# 02_SRAD_Avionics.net
KiCad netlist of a schematic drawn in Altium Designer
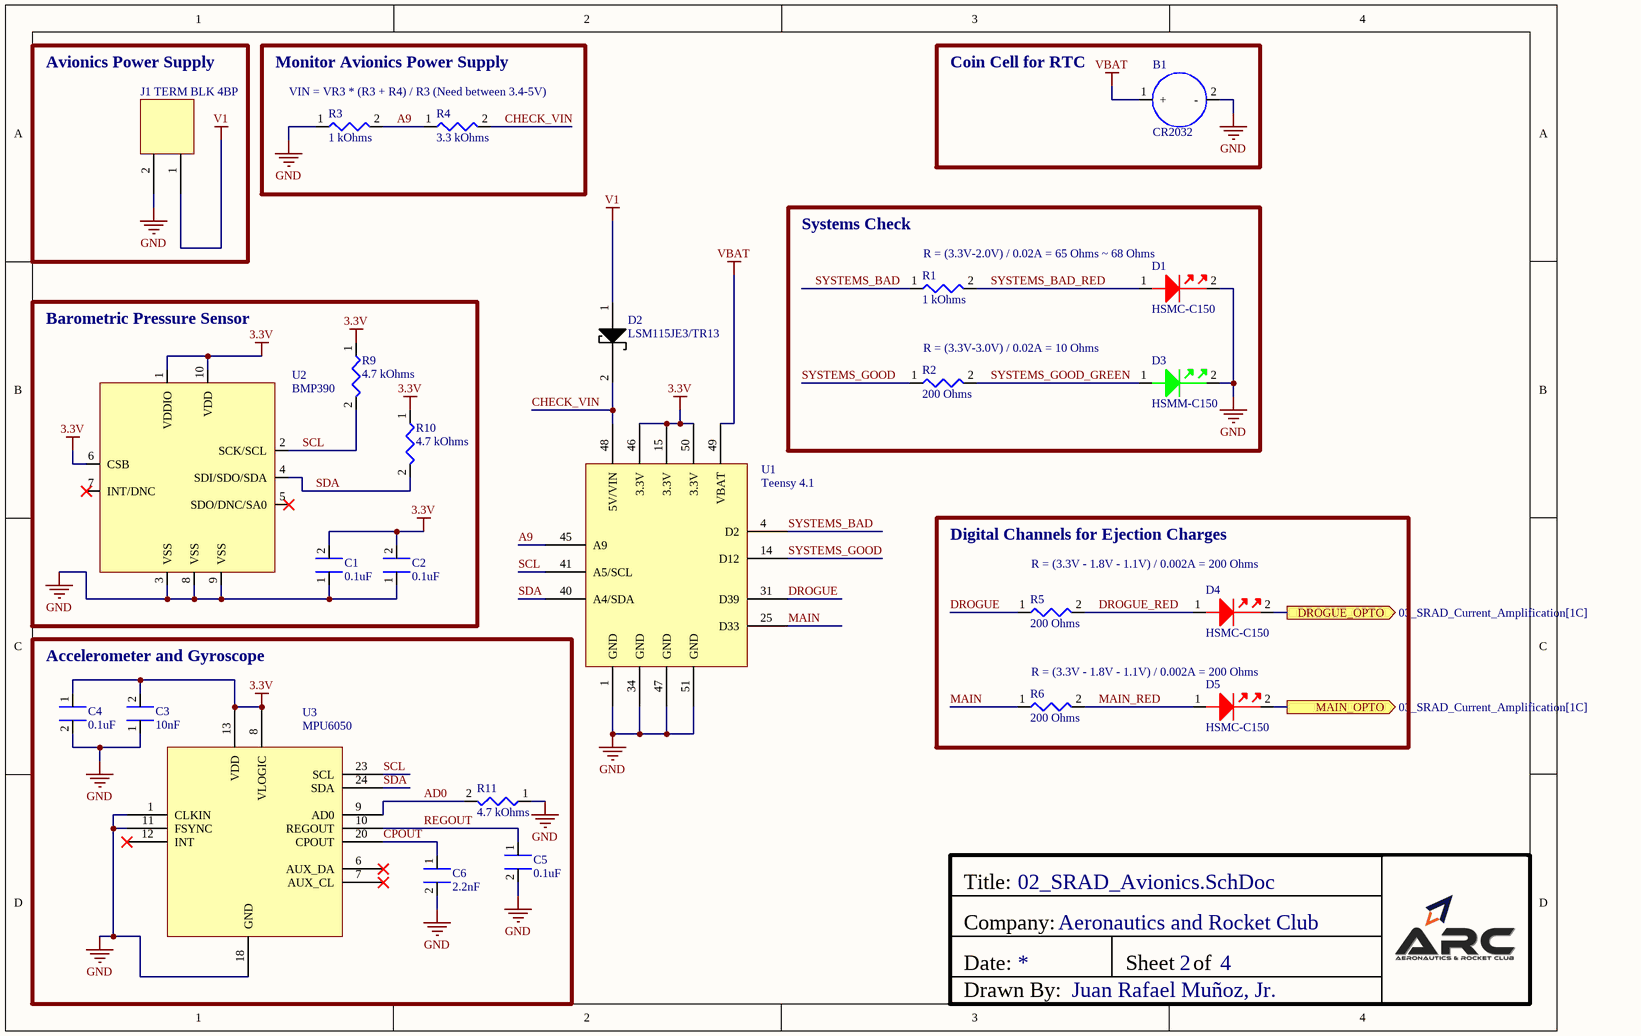
[diagram p0: 02_SRAD_Avionics.SchDoc]

(export (version "E")
  (design (tool "Eeschema 10.0.6"))
  (components
    (comp (ref "B1")
      (value "CR2032")
      (footprint "CR2032")
      (description "CR2032 Coin cell battery of 3V.")
      (libsource (lib "SRAD_SAC_Schlib") (part "CR2032"))
    )
    (comp (ref "C1")
      (value "0.1uF")
      (footprint "CAPC2012X14N_1_35mm_HEIGHT")
      (description "Capacitor Multilayer Ceramic MLCC - SMD/SMT 25 V 0.1uF X7R 0805 5%")
      (fields
        (field (name "MANUFACTURER") "Yageo")
        (field (name "MANUFACTURER PART NUMBER") "CC0805JPX7R8BB104")
      )
      (libsource (lib "SRAD_SAC_Schlib") (part "CC0805JPX7R8BB104"))
    )
    (comp (ref "C2")
      (value "0.1uF")
      (footprint "CAPC2012X14N_1_35mm_HEIGHT")
      (description "Capacitor Multilayer Ceramic MLCC - SMD/SMT 25 V 0.1uF X7R 0805 5%")
      (fields
        (field (name "MANUFACTURER") "Yageo")
        (field (name "MANUFACTURER PART NUMBER") "CC0805JPX7R8BB104")
      )
      (libsource (lib "SRAD_SAC_Schlib") (part "CC0805JPX7R8BB104"))
    )
    (comp (ref "C3")
      (value "10nF")
      (footprint "CAPC2012X07N_06mmHEIGHT")
      (description "Capacitor Multilayer Ceramic MLCC - SMD/SMT 50V 10nF X7R 0805 5%")
      (fields
        (field (name "MANUFACTURER") "Yageo")
        (field (name "MANUFACTURER PART NUMBER") "CC0805JRX7R9BB103")
      )
      (libsource (lib "SRAD_SAC_Schlib") (part "CC0805JRX7R9BB103"))
    )
    (comp (ref "C4")
      (value "0.1uF")
      (footprint "CAPC2012X14N_1_35mm_HEIGHT")
      (description "Capacitor Multilayer Ceramic MLCC - SMD/SMT 25 V 0.1uF X7R 0805 5%")
      (fields
        (field (name "MANUFACTURER") "Yageo")
        (field (name "MANUFACTURER PART NUMBER") "CC0805JPX7R8BB104")
      )
      (libsource (lib "SRAD_SAC_Schlib") (part "CC0805JPX7R8BB104"))
    )
    (comp (ref "C5")
      (value "0.1uF")
      (footprint "CAPC2012X14N_1_35mm_HEIGHT")
      (description "Capacitor Multilayer Ceramic MLCC - SMD/SMT 25 V 0.1uF X7R 0805 5%")
      (fields
        (field (name "MANUFACTURER") "Yageo")
        (field (name "MANUFACTURER PART NUMBER") "CC0805JPX7R8BB104")
      )
      (libsource (lib "SRAD_SAC_Schlib") (part "CC0805JPX7R8BB104"))
    )
    (comp (ref "C6")
      (value "2.2nF")
      (footprint "CAPC2012X07N_06mmHEIGHT")
      (description "Capacitor Multilayer Ceramic MLCC - SMD/SMT 50 V 2.2nF X7R 0805 5%")
      (fields
        (field (name "MANUFACTURER") "Yageo")
        (field (name "MANUFACTURER PART NUMBER") "CC0805JRX7R9BB222")
      )
      (libsource (lib "SRAD_SAC_Schlib") (part "CC0805JRX7R9BB222"))
    )
    (comp (ref "D1")
      (value "HSMC-C150")
      (footprint "DIOM3216X12N RED")
      (description "Red 626nm LED Indication - Discrete 1.9V 1206 (3216 Metric)")
      (fields (field (name "MANUFACTURER") "Broadcom Avago"))
      (libsource (lib "SRAD_SAC_Schlib") (part "DIOM3216X12N RED"))
    )
    (comp (ref "D2")
      (value "LSM115JE3/TR13")
      (footprint "DIOM4336X33N")
      (fields (field (name "MANUFACTURER") "Microchip"))
      (libsource (lib "SRAD_SAC_Schlib") (part "DIOM4336X33N Schottky Diode"))
    )
    (comp (ref "D3")
      (value "HSMM-C150")
      (footprint "DIOM3216X12N GREEN")
      (description "Green 525nm LED Indication - Discrete 3.3V 1206 (3216 Metric)")
      (fields (field (name "MANUFACTURER") "Broadcom Avago"))
      (libsource (lib "SRAD_SAC_Schlib") (part "DIOM3216X12N GREEN"))
    )
    (comp (ref "D4")
      (value "HSMC-C150")
      (footprint "DIOM3216X12N RED")
      (description "Red 626nm LED Indication - Discrete 1.9V 1206 (3216 Metric)")
      (fields (field (name "MANUFACTURER") "Broadcom Avago"))
      (libsource (lib "SRAD_SAC_Schlib") (part "DIOM3216X12N RED"))
    )
    (comp (ref "D5")
      (value "HSMC-C150")
      (footprint "DIOM3216X12N RED")
      (description "Red 626nm LED Indication - Discrete 1.9V 1206 (3216 Metric)")
      (fields (field (name "MANUFACTURER") "Broadcom Avago"))
      (libsource (lib "SRAD_SAC_Schlib") (part "DIOM3216X12N RED"))
    )
    (comp (ref "J1")
      (value "TERM BLK 4BP")
      (footprint "PCB TERM BLK 2P 2.54MM")
      (fields
        (field (name "MANUFACTURER") "TE Connectivity")
        (field (name "MANUFACTURER PART NUMBER") "282834-2")
        (field (name "VOLTAGE") "150V")
      )
      (libsource (lib "SRAD_SAC_Schlib") (part "PCB TERM BLK 2P 2.54MM"))
    )
    (comp (ref "R1")
      (value "1 kOhms")
      (footprint "RESC2012X06N")
      (description "1 kOhms ±1% 0.25W, 1/4W Chip Resistor 0805 (2012 Metric) Moisture Resistant Thick Film")
      (fields
        (field (name "MANUFACTURER") "Yageo")
        (field (name "MANUFACTURER PART NUMBER") "RC0805FR-7W1KL")
      )
      (libsource (lib "SRAD_SAC_Schlib") (part "RC0805FR-7W1KL Yageo"))
    )
    (comp (ref "R2")
      (value "200 Ohms")
      (footprint "RESC2012X06N")
      (description "200 Ohms ±1% 0.25W, 1/4W Chip Resistor 0805 (2012 Metric) Moisture Resistant Thick Film")
      (fields
        (field (name "MANUFACTURER") "Yageo")
        (field (name "MANUFACTURER PART NUMBER") "RC0805FR-7W200RL")
      )
      (libsource (lib "SRAD_SAC_Schlib") (part "RC0805FR-7W200RL Yageo"))
    )
    (comp (ref "R3")
      (value "1 kOhms")
      (footprint "RESC2012X06N")
      (description "1 kOhms ±1% 0.25W, 1/4W Chip Resistor 0805 (2012 Metric) Moisture Resistant Thick Film")
      (fields
        (field (name "MANUFACTURER") "Yageo")
        (field (name "MANUFACTURER PART NUMBER") "RC0805FR-7W1KL")
      )
      (libsource (lib "SRAD_SAC_Schlib") (part "RC0805FR-7W1KL Yageo"))
    )
    (comp (ref "R4")
      (value "3.3 kOhms")
      (footprint "RESC2012X06N")
      (description "3.3 kOhms ±1% 0.25W, 1/4W Chip Resistor 0805 (2012 Metric) Moisture Resistant Thick Film")
      (fields
        (field (name "MANUFACTURER") "Yageo")
        (field (name "MANUFACTURER PART NUMBER") "RC0805FR-7W3K3L")
      )
      (libsource (lib "SRAD_SAC_Schlib") (part "RC0805FR-7W3K3L Yageo"))
    )
    (comp (ref "R5")
      (value "200 Ohms")
      (footprint "RESC2012X06N")
      (description "200 Ohms ±1% 0.25W, 1/4W Chip Resistor 0805 (2012 Metric) Moisture Resistant Thick Film")
      (fields
        (field (name "MANUFACTURER") "Yageo")
        (field (name "MANUFACTURER PART NUMBER") "RC0805FR-7W200RL")
      )
      (libsource (lib "SRAD_SAC_Schlib") (part "RC0805FR-7W200RL Yageo"))
    )
    (comp (ref "R6")
      (value "200 Ohms")
      (footprint "RESC2012X06N")
      (description "200 Ohms ±1% 0.25W, 1/4W Chip Resistor 0805 (2012 Metric) Moisture Resistant Thick Film")
      (fields
        (field (name "MANUFACTURER") "Yageo")
        (field (name "MANUFACTURER PART NUMBER") "RC0805FR-7W200RL")
      )
      (libsource (lib "SRAD_SAC_Schlib") (part "RC0805FR-7W200RL Yageo"))
    )
    (comp (ref "R9")
      (value "4.7 kOhms")
      (footprint "RESC2012X06N")
      (description "4.7 kOhms ±1% 0.25W, 1/4W Chip Resistor 0805 (2012 Metric) Moisture Resistant Thick Film")
      (fields
        (field (name "MANUFACTURER") "Yageo")
        (field (name "MANUFACTURER PART NUMBER") "RC0805FR-7W4K7L")
      )
      (libsource (lib "SRAD_SAC_Schlib") (part "RC0805FR-7W4K7L Yageo"))
    )
    (comp (ref "R10")
      (value "4.7 kOhms")
      (footprint "RESC2012X06N")
      (description "4.7 kOhms ±1% 0.25W, 1/4W Chip Resistor 0805 (2012 Metric) Moisture Resistant Thick Film")
      (fields
        (field (name "MANUFACTURER") "Yageo")
        (field (name "MANUFACTURER PART NUMBER") "RC0805FR-7W4K7L")
      )
      (libsource (lib "SRAD_SAC_Schlib") (part "RC0805FR-7W4K7L Yageo"))
    )
    (comp (ref "R11")
      (value "4.7 kOhms")
      (footprint "RESC2012X06N")
      (description "4.7 kOhms ±1% 0.25W, 1/4W Chip Resistor 0805 (2012 Metric) Moisture Resistant Thick Film")
      (fields
        (field (name "MANUFACTURER") "Yageo")
        (field (name "MANUFACTURER PART NUMBER") "RC0805FR-7W4K7L")
      )
      (libsource (lib "SRAD_SAC_Schlib") (part "RC0805FR-7W4K7L Yageo"))
    )
    (comp (ref "U1")
      (value "Teensy 4.1")
      (footprint "Teensy 4.1")
      (fields (field (name "MANUFACTURER") "SparkFun") (field (name "MANUFACTURER PART NUMBER") "DEV-16996"))
      (libsource (lib "SRAD_SAC_Schlib") (part "Teensy 4.1"))
    )
    (comp (ref "U2")
      (value "BMP390")
      (footprint "BMP390")
      (description "Barometric pressure sensor manufactured by Bosch.")
      (libsource (lib "SRAD_SAC_Schlib") (part "BMP390"))
    )
    (comp (ref "U3")
      (value "MPU6050")
      (footprint "MPU6050")
      (libsource (lib "SRAD_SAC_Schlib") (part "MPU6050"))
    )
  )
  (nets
    (net (code "1") (name "/A9") (class "Default")
      (node (ref "R3") (pin "2") (pinfunction "2_2") (pintype "passive"))
      (node (ref "R4") (pin "1") (pinfunction "1_1") (pintype "passive"))
      (node (ref "U1") (pin "45") (pinfunction "A9_45") (pintype "passive"))
    )
    (net (code "2") (name "/AD0") (class "Default")
      (node (ref "R11") (pin "2") (pinfunction "2_2") (pintype "passive"))
      (node (ref "U3") (pin "9") (pinfunction "AD0_9") (pintype "passive"))
    )
    (net (code "3") (name "/CHECK_VIN") (class "Default")
      (node (ref "D2") (pin "2") (pinfunction "-_2") (pintype "passive"))
      (node (ref "R4") (pin "2") (pinfunction "2_2") (pintype "passive"))
      (node (ref "U1") (pin "48") (pinfunction "5V/VIN_48") (pintype "passive"))
    )
    (net (code "4") (name "/CPOUT") (class "Default")
      (node (ref "C6") (pin "1") (pinfunction "1_1") (pintype "passive"))
      (node (ref "U3") (pin "20") (pinfunction "CPOUT_20") (pintype "passive"))
    )
    (net (code "5") (name "/DROGUE") (class "Default")
      (node (ref "R5") (pin "1") (pinfunction "1_1") (pintype "passive"))
      (node (ref "U1") (pin "31") (pinfunction "D39_31") (pintype "passive"))
    )
    (net (code "6") (name "/DROGUE_OPTO") (class "Default")
      (node (ref "D4") (pin "2") (pinfunction "-_2") (pintype "passive"))
    )
    (net (code "7") (name "/DROGUE_RED") (class "Default")
      (node (ref "D4") (pin "1") (pinfunction "+_1") (pintype "passive"))
      (node (ref "R5") (pin "2") (pinfunction "2_2") (pintype "passive"))
    )
    (net (code "8") (name "/MAIN") (class "Default")
      (node (ref "R6") (pin "1") (pinfunction "1_1") (pintype "passive"))
      (node (ref "U1") (pin "25") (pinfunction "D33_25") (pintype "passive"))
    )
    (net (code "9") (name "/MAIN_OPTO") (class "Default")
      (node (ref "D5") (pin "2") (pinfunction "-_2") (pintype "passive"))
    )
    (net (code "10") (name "/MAIN_RED") (class "Default")
      (node (ref "D5") (pin "1") (pinfunction "+_1") (pintype "passive"))
      (node (ref "R6") (pin "2") (pinfunction "2_2") (pintype "passive"))
    )
    (net (code "11") (name "/REGOUT") (class "Default")
      (node (ref "C5") (pin "1") (pinfunction "1_1") (pintype "passive"))
      (node (ref "U3") (pin "10") (pinfunction "REGOUT_10") (pintype "passive"))
    )
    (net (code "12") (name "/SCL") (class "Default")
      (node (ref "R9") (pin "2") (pinfunction "2_2") (pintype "passive"))
      (node (ref "U1") (pin "41") (pinfunction "A5/SCL_41") (pintype "passive"))
      (node (ref "U2") (pin "2") (pinfunction "SCK/SCL_2") (pintype "passive"))
      (node (ref "U3") (pin "23") (pinfunction "SCL_23") (pintype "passive"))
    )
    (net (code "13") (name "/SDA") (class "Default")
      (node (ref "R10") (pin "2") (pinfunction "2_2") (pintype "passive"))
      (node (ref "U1") (pin "40") (pinfunction "A4/SDA_40") (pintype "passive"))
      (node (ref "U2") (pin "4") (pinfunction "SDI/SDO/SDA_4") (pintype "passive"))
      (node (ref "U3") (pin "24") (pinfunction "SDA_24") (pintype "passive"))
    )
    (net (code "14") (name "/SYSTEMS_BAD") (class "Default")
      (node (ref "R1") (pin "1") (pinfunction "1_1") (pintype "passive"))
      (node (ref "U1") (pin "4") (pinfunction "D2_4") (pintype "passive"))
    )
    (net (code "15") (name "/SYSTEMS_BAD_RED") (class "Default")
      (node (ref "D1") (pin "1") (pinfunction "+_1") (pintype "passive"))
      (node (ref "R1") (pin "2") (pinfunction "2_2") (pintype "passive"))
    )
    (net (code "16") (name "/SYSTEMS_GOOD") (class "Default")
      (node (ref "R2") (pin "1") (pinfunction "1_1") (pintype "passive"))
      (node (ref "U1") (pin "14") (pinfunction "D12_14") (pintype "passive"))
    )
    (net (code "17") (name "/SYSTEMS_GOOD_GREEN") (class "Default")
      (node (ref "D3") (pin "1") (pinfunction "+_1") (pintype "passive"))
      (node (ref "R2") (pin "2") (pinfunction "2_2") (pintype "passive"))
    )
    (net (code "18") (name "3.3V") (class "Default")
      (node (ref "C1") (pin "2") (pinfunction "2_2") (pintype "passive"))
      (node (ref "C2") (pin "2") (pinfunction "2_2") (pintype "passive"))
      (node (ref "C3") (pin "2") (pinfunction "2_2") (pintype "passive"))
      (node (ref "C4") (pin "1") (pinfunction "1_1") (pintype "passive"))
      (node (ref "R10") (pin "1") (pinfunction "1_1") (pintype "passive"))
      (node (ref "R9") (pin "1") (pinfunction "1_1") (pintype "passive"))
      (node (ref "U1") (pin "15") (pinfunction "3.3V_15") (pintype "passive"))
      (node (ref "U1") (pin "46") (pinfunction "3.3V_46") (pintype "passive"))
      (node (ref "U1") (pin "50") (pinfunction "3.3V_50") (pintype "passive"))
      (node (ref "U2") (pin "1") (pinfunction "VDDIO_1") (pintype "passive"))
      (node (ref "U2") (pin "10") (pinfunction "VDD_10") (pintype "passive"))
      (node (ref "U2") (pin "6") (pinfunction "CSB_6") (pintype "passive"))
      (node (ref "U3") (pin "13") (pinfunction "VDD_13") (pintype "passive"))
      (node (ref "U3") (pin "8") (pinfunction "VLOGIC_8") (pintype "passive"))
    )
    (net (code "19") (name "GND") (class "Default")
      (node (ref "B1") (pin "2") (pinfunction "-_2") (pintype "passive"))
      (node (ref "C1") (pin "1") (pinfunction "1_1") (pintype "passive"))
      (node (ref "C2") (pin "1") (pinfunction "1_1") (pintype "passive"))
      (node (ref "C3") (pin "1") (pinfunction "1_1") (pintype "passive"))
      (node (ref "C4") (pin "2") (pinfunction "2_2") (pintype "passive"))
      (node (ref "C5") (pin "2") (pinfunction "2_2") (pintype "passive"))
      (node (ref "C6") (pin "2") (pinfunction "2_2") (pintype "passive"))
      (node (ref "D1") (pin "2") (pinfunction "-_2") (pintype "passive"))
      (node (ref "D3") (pin "2") (pinfunction "-_2") (pintype "passive"))
      (node (ref "J1") (pin "2") (pinfunction "-_2") (pintype "passive"))
      (node (ref "R11") (pin "1") (pinfunction "1_1") (pintype "passive"))
      (node (ref "R3") (pin "1") (pinfunction "1_1") (pintype "passive"))
      (node (ref "U1") (pin "1") (pinfunction "GND_1") (pintype "passive"))
      (node (ref "U1") (pin "34") (pinfunction "GND_34") (pintype "passive"))
      (node (ref "U1") (pin "47") (pinfunction "GND_47") (pintype "passive"))
      (node (ref "U1") (pin "51") (pinfunction "GND_51") (pintype "passive"))
      (node (ref "U2") (pin "3") (pinfunction "VSS_3") (pintype "passive"))
      (node (ref "U2") (pin "8") (pinfunction "VSS_8") (pintype "passive"))
      (node (ref "U2") (pin "9") (pinfunction "VSS_9") (pintype "passive"))
      (node (ref "U3") (pin "1") (pinfunction "CLKIN_1") (pintype "passive"))
      (node (ref "U3") (pin "11") (pinfunction "FSYNC_11") (pintype "passive"))
      (node (ref "U3") (pin "18") (pinfunction "GND_18") (pintype "passive"))
    )
    (net (code "20") (name "V1") (class "Default")
      (node (ref "D2") (pin "1") (pinfunction "+_1") (pintype "passive"))
      (node (ref "J1") (pin "1") (pinfunction "+_1") (pintype "passive"))
    )
    (net (code "21") (name "VBAT") (class "Default")
      (node (ref "B1") (pin "1") (pinfunction "+_1") (pintype "passive"))
      (node (ref "U1") (pin "49") (pinfunction "VBAT_49") (pintype "passive"))
    )
    (net (code "22") (name "unconnected-(U2-INT{slash}DNC-Pad7)") (class "Default")
      (node (ref "U2") (pin "7") (pinfunction "INT/DNC_7") (pintype "passive+no_connect"))
    )
    (net (code "23") (name "unconnected-(U2-SDO{slash}DNC{slash}SA0-Pad5)") (class "Default")
      (node (ref "U2") (pin "5") (pinfunction "SDO/DNC/SA0_5") (pintype "passive+no_connect"))
    )
    (net (code "24") (name "unconnected-(U3-AUX_CL-Pad7)") (class "Default")
      (node (ref "U3") (pin "7") (pinfunction "AUX_CL_7") (pintype "passive+no_connect"))
    )
    (net (code "25") (name "unconnected-(U3-AUX_DA-Pad6)") (class "Default")
      (node (ref "U3") (pin "6") (pinfunction "AUX_DA_6") (pintype "passive+no_connect"))
    )
    (net (code "26") (name "unconnected-(U3-INT-Pad12)") (class "Default")
      (node (ref "U3") (pin "12") (pinfunction "INT_12") (pintype "passive+no_connect"))
    )
  )
)
